# 1_power.net
KiCad netlist of a schematic drawn in Altium Designer
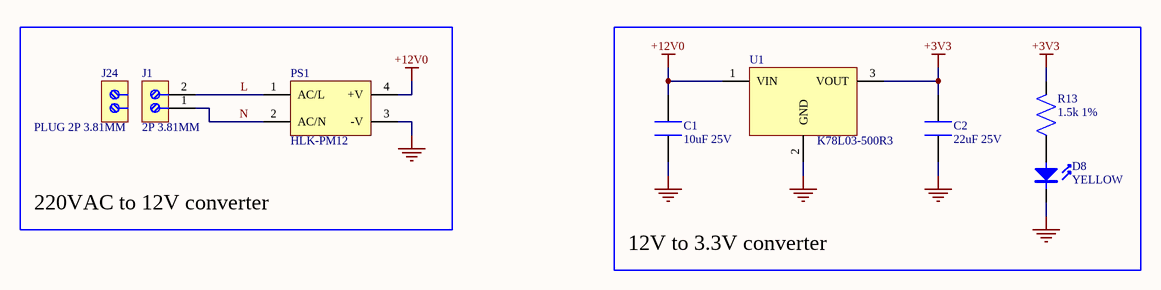
[diagram p0: 1_power.SchDoc]

(export (version "E")
  (design (tool "Eeschema 10.0.6"))
  (components
    (comp (ref "C1")
      (value "10uF 25V")
      (footprint "C0805")
      (description "X5R 25V ±10% 10uF 0805 Multilayer Ceramic Capacitors MLCC - SMD/SMT")
      (fields (field (name "LCSC PART") "C15850"))
      (libsource (lib "nombre_por_definir") (part "CL21A106KAYNNNE"))
    )
    (comp (ref "C2")
      (value "22uF 25V")
      (footprint "C0805")
      (description "X5R 25V ±20% 22uF 0805 Multilayer Ceramic Capacitors MLCC - SMD/SMT")
      (fields (field (name "LCSC PART") "C45783"))
      (libsource (lib "nombre_por_definir") (part "CL21A226MAQNNNE"))
    )
    (comp (ref "D8")
      (value "YELLOW")
      (footprint "LED0603-YELLOW")
      (description "Yellow 585.5~591.5nm 0603 Light Emitting Diodes (LED)")
      (fields (field (name "LCSC PART") "C72038"))
      (libsource (lib "nombre_por_definir") (part "19-213/Y2C-CQ2R2L/3T(CY)"))
    )
    (comp (ref "J1")
      (value "2P 3.81MM")
      (footprint "TB-2P-3.81MM")
      (description "Terminal Block 2 Positions 3.81MM")
      (libsource (lib "nombre_por_definir") (part "TBLOCK-2P-3.81MM"))
    )
    (comp (ref "J24")
      (value "PLUG 2P 3.81MM")
      (footprint "TB-PLUG-2P-3.81MM")
      (description "Terminal block plug 2positions 3.81mm")
      (libsource (lib "nombre_por_definir") (part "PLUG-2P-3.81MM"))
    )
    (comp (ref "PS1")
      (value "HLK-PM12")
      (footprint "HLK-PM12")
      (description "220VAC to 12VDC Power Module 3W")
      (fields (field (name "LCSC PART") "C209905"))
      (libsource (lib "nombre_por_definir") (part "HLK-PM12"))
    )
    (comp (ref "R13")
      (value "1.5k 1%")
      (footprint "R0603")
      (description "1.5kΩ ±1% ±100ppm/℃ 0.1W 0603 Chip Resistor - Surface Mount")
      (fields (field (name "LCSC PART") "C22843"))
      (libsource (lib "nombre_por_definir") (part "0603WAF1501T5E"))
    )
    (comp (ref "U1")
      (value "K78L03-500R3")
      (footprint "K78LXX-500R3")
      (description "36V 500mA 3.3V 1 SIP Power Modules")
      (fields (field (name "LCSC PART") "C115818"))
      (libsource (lib "nombre_por_definir") (part "K78L03-500R3"))
    )
  )
  (nets
    (net (code "1") (name "+3V3") (class "Default")
      (node (ref "C2") (pin "1") (pinfunction "1_1") (pintype "passive"))
      (node (ref "R13") (pin "2") (pinfunction "2_2") (pintype "passive"))
      (node (ref "U1") (pin "3") (pinfunction "VOUT_3") (pintype "passive"))
    )
    (net (code "2") (name "+12V0") (class "Default")
      (node (ref "C1") (pin "1") (pinfunction "1_1") (pintype "passive"))
      (node (ref "PS1") (pin "4") (pinfunction "+V_4") (pintype "passive"))
      (node (ref "U1") (pin "1") (pinfunction "VIN_1") (pintype "passive"))
    )
    (net (code "3") (name "/L") (class "Default")
      (node (ref "J1") (pin "2") (pinfunction "2_2") (pintype "passive"))
      (node (ref "PS1") (pin "1") (pinfunction "AC/L_1") (pintype "passive"))
    )
    (net (code "4") (name "/N") (class "Default")
      (node (ref "J1") (pin "1") (pinfunction "1_1") (pintype "passive"))
      (node (ref "PS1") (pin "2") (pinfunction "AC/N_2") (pintype "passive"))
    )
    (net (code "5") (name "GND") (class "Default")
      (node (ref "C1") (pin "2") (pinfunction "2_2") (pintype "passive"))
      (node (ref "C2") (pin "2") (pinfunction "2_2") (pintype "passive"))
      (node (ref "D8") (pin "1") (pinfunction "1_1") (pintype "passive"))
      (node (ref "PS1") (pin "3") (pinfunction "-V_3") (pintype "passive"))
      (node (ref "U1") (pin "2") (pinfunction "GND_2") (pintype "passive"))
    )
    (net (code "6") (name "Net-(D8-Pad2)") (class "Default")
      (node (ref "D8") (pin "2") (pinfunction "2_2") (pintype "passive"))
      (node (ref "R13") (pin "1") (pinfunction "1_1") (pintype "passive"))
    )
  )
)
